# espnative-deadrail-2-b.net
KiCad netlist of a schematic drawn in EAGLE
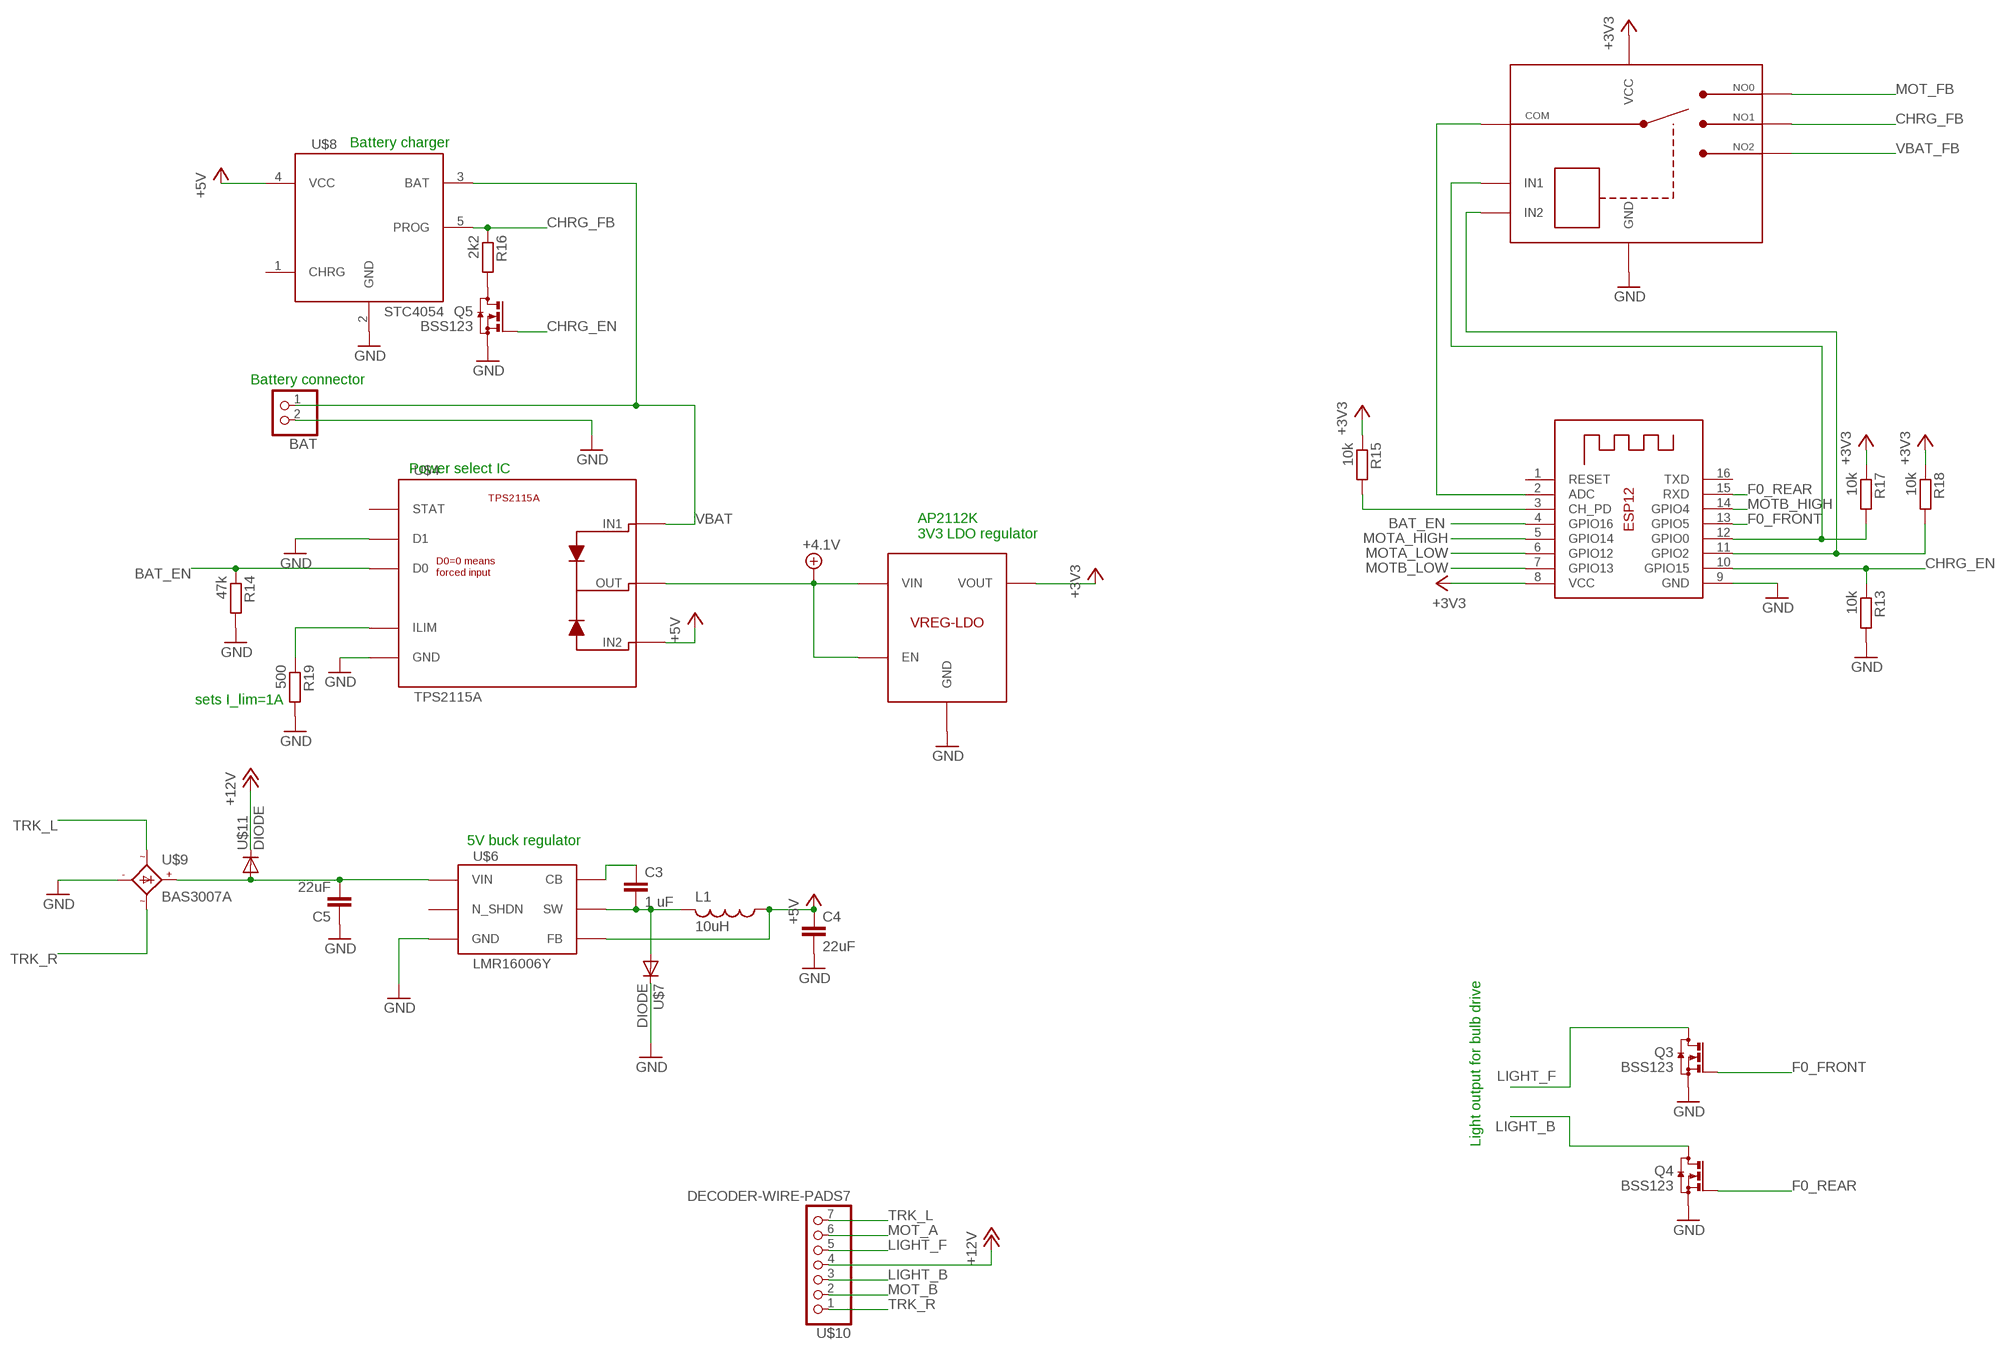
[diagram p0: schematic, sheet 1, part 1 of 2]
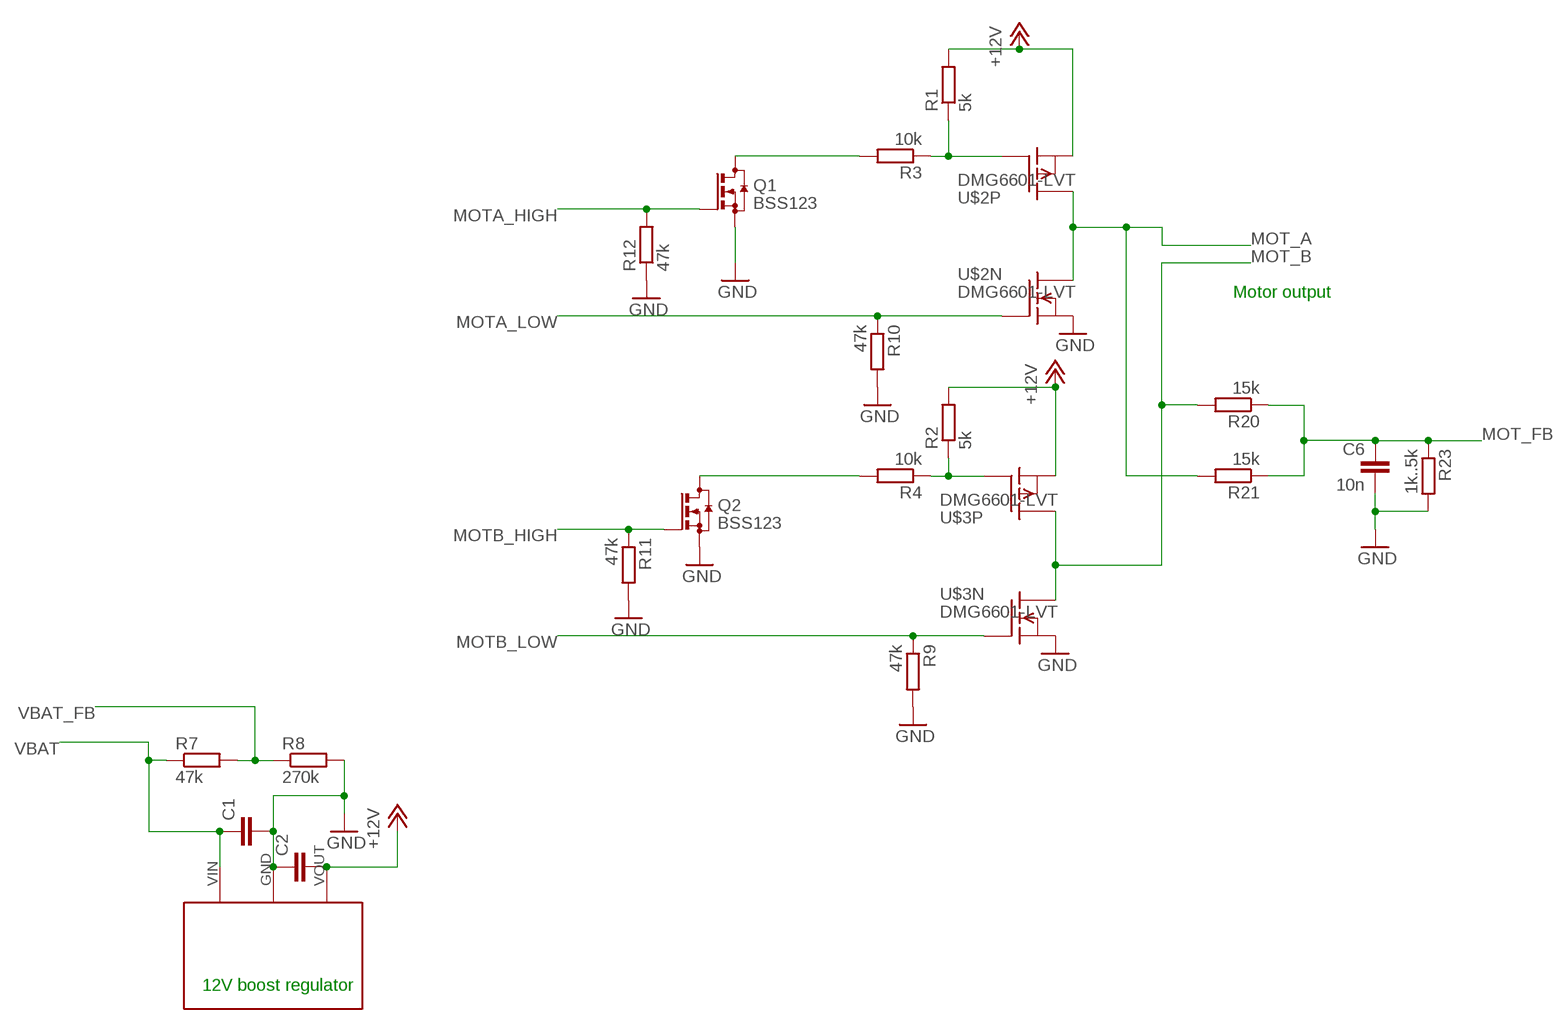
[diagram p1: schematic, sheet 1, part 2 of 2]

(export (version "E")
  (design (tool "Eeschema 10.0.6"))
  (components
    (comp (ref "BAT")
      (value "JST_2PIN-SMT-RA")
      (footprint "eagle-import:JST-PH-2-SMT-RA")
      (libsource (lib "eagle-import") (part "JST_2PIN-SMT-RA"))
    )
    (comp (ref "C1")
      (value "C-EUC1206")
      (footprint "eagle-import:C1206")
      (libsource (lib "eagle-import") (part "C-EUC1206"))
    )
    (comp (ref "C2")
      (value "C-EUC1206")
      (footprint "eagle-import:C1206")
      (libsource (lib "eagle-import") (part "C-EUC1206"))
    )
    (comp (ref "C3")
      (value "1 uF")
      (footprint "eagle-import:C0603")
      (libsource (lib "eagle-import") (part "C-EUC0603"))
    )
    (comp (ref "C4")
      (value "22uF")
      (footprint "eagle-import:C0603")
      (libsource (lib "eagle-import") (part "C-EUC0603"))
    )
    (comp (ref "C5")
      (value "22uF")
      (footprint "eagle-import:C1206")
      (libsource (lib "eagle-import") (part "C-EUC1206"))
    )
    (comp (ref "C6")
      (value "10n")
      (footprint "eagle-import:C0603")
      (libsource (lib "eagle-import") (part "C-EUC0603"))
    )
    (comp (ref "L1")
      (value "10uH")
      (footprint "eagle-import:FDSD0420")
      (libsource (lib "eagle-import") (part "FDSD0420"))
    )
    (comp (ref "Q1")
      (value "BSS123")
      (footprint "eagle-import:SOT23")
      (libsource (lib "eagle-import") (part "BSS123"))
    )
    (comp (ref "Q2")
      (value "BSS123")
      (footprint "eagle-import:SOT23")
      (libsource (lib "eagle-import") (part "BSS123"))
    )
    (comp (ref "Q3")
      (value "BSS123")
      (footprint "eagle-import:SOT23")
      (libsource (lib "eagle-import") (part "BSS123"))
    )
    (comp (ref "Q4")
      (value "BSS123")
      (footprint "eagle-import:SOT23")
      (libsource (lib "eagle-import") (part "BSS123"))
    )
    (comp (ref "Q5")
      (value "BSS123")
      (footprint "eagle-import:SOT23")
      (libsource (lib "eagle-import") (part "BSS123"))
    )
    (comp (ref "R1")
      (value "5k")
      (footprint "eagle-import:R0603")
      (libsource (lib "eagle-import") (part "R-EU_R0603"))
    )
    (comp (ref "R2")
      (value "5k")
      (footprint "eagle-import:R0603")
      (libsource (lib "eagle-import") (part "R-EU_R0603"))
    )
    (comp (ref "R3")
      (value "10k")
      (footprint "eagle-import:R0603")
      (libsource (lib "eagle-import") (part "R-EU_R0603"))
    )
    (comp (ref "R4")
      (value "10k")
      (footprint "eagle-import:R0603")
      (libsource (lib "eagle-import") (part "R-EU_R0603"))
    )
    (comp (ref "R7")
      (value "47k")
      (footprint "eagle-import:R0603")
      (libsource (lib "eagle-import") (part "R-EU_R0603"))
    )
    (comp (ref "R8")
      (value "270k")
      (footprint "eagle-import:R0603")
      (libsource (lib "eagle-import") (part "R-EU_R0603"))
    )
    (comp (ref "R9")
      (value "47k")
      (footprint "eagle-import:R0603")
      (libsource (lib "eagle-import") (part "R-EU_R0603"))
    )
    (comp (ref "R10")
      (value "47k")
      (footprint "eagle-import:R0603")
      (libsource (lib "eagle-import") (part "R-EU_R0603"))
    )
    (comp (ref "R11")
      (value "47k")
      (footprint "eagle-import:R0603")
      (libsource (lib "eagle-import") (part "R-EU_R0603"))
    )
    (comp (ref "R12")
      (value "47k")
      (footprint "eagle-import:R0603")
      (libsource (lib "eagle-import") (part "R-EU_R0603"))
    )
    (comp (ref "R13")
      (value "10k")
      (footprint "eagle-import:R0603")
      (libsource (lib "eagle-import") (part "R-EU_R0603"))
    )
    (comp (ref "R14")
      (value "47k")
      (footprint "eagle-import:R0603")
      (libsource (lib "eagle-import") (part "R-EU_R0603"))
    )
    (comp (ref "R15")
      (value "10k")
      (footprint "eagle-import:R0603")
      (libsource (lib "eagle-import") (part "R-EU_R0603"))
    )
    (comp (ref "R16")
      (value "2k2")
      (footprint "eagle-import:R0603")
      (libsource (lib "eagle-import") (part "R-EU_R0603"))
    )
    (comp (ref "R17")
      (value "10k")
      (footprint "eagle-import:R0603")
      (libsource (lib "eagle-import") (part "R-EU_R0603"))
    )
    (comp (ref "R18")
      (value "10k")
      (footprint "eagle-import:R0603")
      (libsource (lib "eagle-import") (part "R-EU_R0603"))
    )
    (comp (ref "R19")
      (value "500")
      (footprint "eagle-import:R0603")
      (libsource (lib "eagle-import") (part "R-EU_R0603"))
    )
    (comp (ref "R20")
      (value "15k")
      (footprint "eagle-import:R0603")
      (libsource (lib "eagle-import") (part "R-EU_R0603"))
    )
    (comp (ref "R21")
      (value "15k")
      (footprint "eagle-import:R0603")
      (libsource (lib "eagle-import") (part "R-EU_R0603"))
    )
    (comp (ref "R23")
      (value "1k..5k")
      (footprint "eagle-import:R0603")
      (libsource (lib "eagle-import") (part "R-EU_R0603"))
    )
    (comp (ref "U$1")
      (value "AP2112K-3V3")
      (footprint "eagle-import:SOT23-5L")
      (libsource (lib "eagle-import") (part "AP2112K"))
    )
    (comp (ref "U$2")
      (value "DMG6601-LVT")
      (footprint "eagle-import:TSOT-26")
      (libsource (lib "eagle-import") (part "DMG6601-LVT"))
    )
    (comp (ref "U$3")
      (value "DMG6601-LVT")
      (footprint "eagle-import:TSOT-26")
      (libsource (lib "eagle-import") (part "DMG6601-LVT"))
    )
    (comp (ref "U$4")
      (value "TPS2115A")
      (footprint "eagle-import:TSSOP-8")
      (libsource (lib "eagle-import") (part "TPS2115A"))
    )
    (comp (ref "U$5")
      (value "POLOLU-VREG12")
      (footprint "eagle-import:POLOLU-REGULATOR")
      (libsource (lib "eagle-import") (part "POLOLU-VREG12"))
    )
    (comp (ref "U$6")
      (value "LMR16006Y")
      (footprint "eagle-import:SOT23-6")
      (libsource (lib "eagle-import") (part "LMR16006Y"))
    )
    (comp (ref "U$7")
      (value "DIODE")
      (footprint "eagle-import:DIODE-1206")
      (libsource (lib "eagle-import") (part "DIODE"))
    )
    (comp (ref "U$8")
      (value "STC4054")
      (footprint "eagle-import:SOT23-5L")
      (libsource (lib "eagle-import") (part "STC4054"))
    )
    (comp (ref "U$9")
      (value "BAS3007A")
      (footprint "eagle-import:SOT143B")
      (libsource (lib "eagle-import") (part "BAS3007A"))
    )
    (comp (ref "U$10")
      (value "DECODER-WIRE-PADS7")
      (footprint "eagle-import:DECODER-WIRE-PADS")
      (libsource (lib "eagle-import") (part "DECODER-WIRE-PADS7"))
    )
    (comp (ref "U$11")
      (value "DIODE")
      (footprint "eagle-import:DIODE-1206")
      (libsource (lib "eagle-import") (part "DIODE"))
    )
    (comp (ref "U$12")
      (value "TS5A3359")
      (footprint "eagle-import:US8")
      (libsource (lib "eagle-import") (part "TS5A3359"))
    )
    (comp (ref "X1")
      (value "ESP-12")
      (footprint "eagle-import:ESP-12")
      (libsource (lib "eagle-import") (part "ESP-12"))
    )
  )
  (nets
    (net (code "1") (name "+3V3") (class "Default")
      (node (ref "R15") (pin "1") (pinfunction "1_1") (pintype "passive"))
      (node (ref "R17") (pin "1") (pinfunction "1_1") (pintype "passive"))
      (node (ref "R18") (pin "1") (pinfunction "1_1") (pintype "passive"))
      (node (ref "U$1") (pin "5") (pinfunction "VOUT_5") (pintype "bidirectional"))
      (node (ref "U$12") (pin "8") (pinfunction "VCC_8") (pintype "bidirectional"))
      (node (ref "X1") (pin "8") (pinfunction "VCC_8") (pintype "power_in"))
    )
    (net (code "2") (name "+4.1V") (class "Default")
      (node (ref "U$1") (pin "1") (pinfunction "VIN_1") (pintype "bidirectional"))
      (node (ref "U$1") (pin "3") (pinfunction "EN_3") (pintype "bidirectional"))
      (node (ref "U$4") (pin "7") (pinfunction "OUT_7") (pintype "bidirectional"))
    )
    (net (code "3") (name "+5V") (class "Default")
      (node (ref "C4") (pin "1") (pinfunction "1_1") (pintype "passive"))
      (node (ref "L1") (pin "P$1") (pinfunction "1_P$1") (pintype "passive"))
      (node (ref "U$4") (pin "6") (pinfunction "IN2_6") (pintype "bidirectional"))
      (node (ref "U$6") (pin "3") (pinfunction "FB_3") (pintype "bidirectional"))
      (node (ref "U$8") (pin "4") (pinfunction "VCC_4") (pintype "bidirectional"))
    )
    (net (code "4") (name "+12V") (class "Default")
      (node (ref "C2") (pin "2") (pinfunction "2_2") (pintype "passive"))
      (node (ref "R1") (pin "2") (pinfunction "2_2") (pintype "passive"))
      (node (ref "R2") (pin "2") (pinfunction "2_2") (pintype "passive"))
      (node (ref "U$10") (pin "4") (pinfunction "4_4") (pintype "passive"))
      (node (ref "U$11") (pin "C") (pinfunction "C_C") (pintype "passive"))
      (node (ref "U$2") (pin "2") (pinfunction "S_2") (pintype "passive"))
      (node (ref "U$3") (pin "2") (pinfunction "S_2") (pintype "passive"))
      (node (ref "U$5") (pin "VOUT") (pinfunction "VOUT_VOUT") (pintype "bidirectional"))
    )
    (net (code "5") (name "/BAT_EN") (class "Default")
      (node (ref "R14") (pin "1") (pinfunction "1_1") (pintype "passive"))
      (node (ref "U$4") (pin "2") (pinfunction "D0_2") (pintype "bidirectional"))
      (node (ref "X1") (pin "4") (pinfunction "GPIO16_4") (pintype "bidirectional"))
    )
    (net (code "6") (name "/CHRG_EN") (class "Default")
      (node (ref "Q5") (pin "1") (pinfunction "G_1") (pintype "passive"))
      (node (ref "R13") (pin "1") (pinfunction "1_1") (pintype "passive"))
      (node (ref "X1") (pin "10") (pinfunction "GPIO15_10") (pintype "bidirectional"))
    )
    (net (code "7") (name "/CHRG_FB") (class "Default")
      (node (ref "R16") (pin "1") (pinfunction "1_1") (pintype "passive"))
      (node (ref "U$12") (pin "2") (pinfunction "NO1_2") (pintype "bidirectional"))
      (node (ref "U$8") (pin "5") (pinfunction "PROG_5") (pintype "bidirectional"))
    )
    (net (code "8") (name "/F0_FRONT") (class "Default")
      (node (ref "Q3") (pin "1") (pinfunction "G_1") (pintype "passive"))
      (node (ref "X1") (pin "13") (pinfunction "GPIO5_13") (pintype "bidirectional"))
    )
    (net (code "9") (name "/F0_REAR") (class "Default")
      (node (ref "Q4") (pin "1") (pinfunction "G_1") (pintype "passive"))
      (node (ref "X1") (pin "15") (pinfunction "RXD_15") (pintype "input"))
    )
    (net (code "10") (name "/LIGHT_B") (class "Default")
      (node (ref "Q4") (pin "3") (pinfunction "D_3") (pintype "passive"))
      (node (ref "U$10") (pin "3") (pinfunction "3_3") (pintype "passive"))
    )
    (net (code "11") (name "/LIGHT_F") (class "Default")
      (node (ref "Q3") (pin "3") (pinfunction "D_3") (pintype "passive"))
      (node (ref "U$10") (pin "5") (pinfunction "5_5") (pintype "passive"))
    )
    (net (code "12") (name "/MOTA_HIGH") (class "Default")
      (node (ref "Q1") (pin "1") (pinfunction "G_1") (pintype "passive"))
      (node (ref "R12") (pin "2") (pinfunction "2_2") (pintype "passive"))
      (node (ref "X1") (pin "5") (pinfunction "GPIO14_5") (pintype "bidirectional"))
    )
    (net (code "13") (name "/MOTA_LOW") (class "Default")
      (node (ref "R10") (pin "1") (pinfunction "1_1") (pintype "passive"))
      (node (ref "U$2") (pin "1") (pinfunction "G_1") (pintype "passive"))
      (node (ref "X1") (pin "6") (pinfunction "GPIO12_6") (pintype "bidirectional"))
    )
    (net (code "14") (name "/MOTB_HIGH") (class "Default")
      (node (ref "Q2") (pin "1") (pinfunction "G_1") (pintype "passive"))
      (node (ref "R11") (pin "1") (pinfunction "1_1") (pintype "passive"))
      (node (ref "X1") (pin "14") (pinfunction "GPIO4_14") (pintype "bidirectional"))
    )
    (net (code "15") (name "/MOTB_LOW") (class "Default")
      (node (ref "R9") (pin "1") (pinfunction "1_1") (pintype "passive"))
      (node (ref "U$3") (pin "1") (pinfunction "G_1") (pintype "passive"))
      (node (ref "X1") (pin "7") (pinfunction "GPIO13_7") (pintype "bidirectional"))
    )
    (net (code "16") (name "/MOT_A") (class "Default")
      (node (ref "R21") (pin "2") (pinfunction "2_2") (pintype "passive"))
      (node (ref "U$10") (pin "6") (pinfunction "6_6") (pintype "passive"))
      (node (ref "U$2") (pin "4") (pinfunction "D_4") (pintype "passive"))
      (node (ref "U$2") (pin "6") (pinfunction "D_6") (pintype "passive"))
    )
    (net (code "17") (name "/MOT_B") (class "Default")
      (node (ref "R20") (pin "2") (pinfunction "2_2") (pintype "passive"))
      (node (ref "U$10") (pin "2") (pinfunction "2_2") (pintype "passive"))
      (node (ref "U$3") (pin "4") (pinfunction "D_4") (pintype "passive"))
      (node (ref "U$3") (pin "6") (pinfunction "D_6") (pintype "passive"))
    )
    (net (code "18") (name "/MOT_FB") (class "Default")
      (node (ref "C6") (pin "1") (pinfunction "1_1") (pintype "passive"))
      (node (ref "R20") (pin "1") (pinfunction "1_1") (pintype "passive"))
      (node (ref "R21") (pin "1") (pinfunction "1_1") (pintype "passive"))
      (node (ref "R23") (pin "1") (pinfunction "1_1") (pintype "passive"))
      (node (ref "U$12") (pin "1") (pinfunction "NO0_1") (pintype "bidirectional"))
    )
    (net (code "19") (name "/TRK_L") (class "Default")
      (node (ref "U$10") (pin "7") (pinfunction "7_7") (pintype "passive"))
      (node (ref "U$9") (pin "2") (pinfunction "AC1_2") (pintype "passive"))
    )
    (net (code "20") (name "/TRK_R") (class "Default")
      (node (ref "U$10") (pin "1") (pinfunction "1_1") (pintype "passive"))
      (node (ref "U$9") (pin "3") (pinfunction "AC2_3") (pintype "passive"))
    )
    (net (code "21") (name "/VBAT") (class "Default")
      (node (ref "BAT") (pin "1") (pinfunction "2_1") (pintype "passive"))
      (node (ref "C1") (pin "1") (pinfunction "1_1") (pintype "passive"))
      (node (ref "R7") (pin "1") (pinfunction "1_1") (pintype "passive"))
      (node (ref "U$4") (pin "8") (pinfunction "IN1_8") (pintype "bidirectional"))
      (node (ref "U$5") (pin "VIN") (pinfunction "VIN_VIN") (pintype "bidirectional"))
      (node (ref "U$8") (pin "3") (pinfunction "BAT_3") (pintype "bidirectional"))
    )
    (net (code "22") (name "/VBAT_FB") (class "Default")
      (node (ref "R7") (pin "2") (pinfunction "2_2") (pintype "passive"))
      (node (ref "R8") (pin "1") (pinfunction "1_1") (pintype "passive"))
      (node (ref "U$12") (pin "3") (pinfunction "NO2_3") (pintype "bidirectional"))
    )
    (net (code "23") (name "GND") (class "Default")
      (node (ref "BAT") (pin "2") (pinfunction "1_2") (pintype "passive"))
      (node (ref "C1") (pin "2") (pinfunction "2_2") (pintype "passive"))
      (node (ref "C2") (pin "1") (pinfunction "1_1") (pintype "passive"))
      (node (ref "C4") (pin "2") (pinfunction "2_2") (pintype "passive"))
      (node (ref "C5") (pin "1") (pinfunction "1_1") (pintype "passive"))
      (node (ref "C6") (pin "2") (pinfunction "2_2") (pintype "passive"))
      (node (ref "Q1") (pin "2") (pinfunction "S_2") (pintype "passive"))
      (node (ref "Q2") (pin "2") (pinfunction "S_2") (pintype "passive"))
      (node (ref "Q3") (pin "2") (pinfunction "S_2") (pintype "passive"))
      (node (ref "Q4") (pin "2") (pinfunction "S_2") (pintype "passive"))
      (node (ref "Q5") (pin "2") (pinfunction "S_2") (pintype "passive"))
      (node (ref "R10") (pin "2") (pinfunction "2_2") (pintype "passive"))
      (node (ref "R11") (pin "2") (pinfunction "2_2") (pintype "passive"))
      (node (ref "R12") (pin "1") (pinfunction "1_1") (pintype "passive"))
      (node (ref "R13") (pin "2") (pinfunction "2_2") (pintype "passive"))
      (node (ref "R14") (pin "2") (pinfunction "2_2") (pintype "passive"))
      (node (ref "R19") (pin "2") (pinfunction "2_2") (pintype "passive"))
      (node (ref "R23") (pin "2") (pinfunction "2_2") (pintype "passive"))
      (node (ref "R8") (pin "2") (pinfunction "2_2") (pintype "passive"))
      (node (ref "R9") (pin "2") (pinfunction "2_2") (pintype "passive"))
      (node (ref "U$1") (pin "2") (pinfunction "GND_2") (pintype "bidirectional"))
      (node (ref "U$12") (pin "4") (pinfunction "GND_4") (pintype "bidirectional"))
      (node (ref "U$2") (pin "5") (pinfunction "S_5") (pintype "passive"))
      (node (ref "U$3") (pin "5") (pinfunction "S_5") (pintype "passive"))
      (node (ref "U$4") (pin "3") (pinfunction "D1_3") (pintype "bidirectional"))
      (node (ref "U$4") (pin "5") (pinfunction "GND_5") (pintype "bidirectional"))
      (node (ref "U$5") (pin "GND") (pinfunction "GND_GND") (pintype "bidirectional"))
      (node (ref "U$6") (pin "2") (pinfunction "GND_2") (pintype "bidirectional"))
      (node (ref "U$7") (pin "C") (pinfunction "C_C") (pintype "passive"))
      (node (ref "U$8") (pin "2") (pinfunction "GND_2") (pintype "bidirectional"))
      (node (ref "U$9") (pin "1") (pinfunction "-_1") (pintype "passive"))
      (node (ref "X1") (pin "9") (pinfunction "GND_9") (pintype "power_in"))
    )
    (net (code "24") (name "Net-(L1-2)") (class "Default")
      (node (ref "C3") (pin "2") (pinfunction "2_2") (pintype "passive"))
      (node (ref "L1") (pin "P$2") (pinfunction "2_P$2") (pintype "passive"))
      (node (ref "U$6") (pin "6") (pinfunction "SW_6") (pintype "bidirectional"))
      (node (ref "U$7") (pin "A") (pinfunction "A_A") (pintype "passive"))
    )
    (net (code "25") (name "Net-(Q1-D)") (class "Default")
      (node (ref "Q1") (pin "3") (pinfunction "D_3") (pintype "passive"))
      (node (ref "R3") (pin "2") (pinfunction "2_2") (pintype "passive"))
    )
    (net (code "26") (name "Net-(Q2-D)") (class "Default")
      (node (ref "Q2") (pin "3") (pinfunction "D_3") (pintype "passive"))
      (node (ref "R4") (pin "2") (pinfunction "2_2") (pintype "passive"))
    )
    (net (code "27") (name "Net-(Q5-D)") (class "Default")
      (node (ref "Q5") (pin "3") (pinfunction "D_3") (pintype "passive"))
      (node (ref "R16") (pin "2") (pinfunction "2_2") (pintype "passive"))
    )
    (net (code "28") (name "Net-(U$2B-G)") (class "Default")
      (node (ref "R1") (pin "1") (pinfunction "1_1") (pintype "passive"))
      (node (ref "R3") (pin "1") (pinfunction "1_1") (pintype "passive"))
      (node (ref "U$2") (pin "3") (pinfunction "G_3") (pintype "passive"))
    )
    (net (code "29") (name "Net-(U$3B-G)") (class "Default")
      (node (ref "R2") (pin "1") (pinfunction "1_1") (pintype "passive"))
      (node (ref "R4") (pin "1") (pinfunction "1_1") (pintype "passive"))
      (node (ref "U$3") (pin "3") (pinfunction "G_3") (pintype "passive"))
    )
    (net (code "30") (name "Net-(U$4-ILIM)") (class "Default")
      (node (ref "R19") (pin "1") (pinfunction "1_1") (pintype "passive"))
      (node (ref "U$4") (pin "4") (pinfunction "ILIM_4") (pintype "bidirectional"))
    )
    (net (code "31") (name "Net-(U$6-CB)") (class "Default")
      (node (ref "C3") (pin "1") (pinfunction "1_1") (pintype "passive"))
      (node (ref "U$6") (pin "1") (pinfunction "CB_1") (pintype "bidirectional"))
    )
    (net (code "32") (name "Net-(U$6-VIN)") (class "Default")
      (node (ref "C5") (pin "2") (pinfunction "2_2") (pintype "passive"))
      (node (ref "U$11") (pin "A") (pinfunction "A_A") (pintype "passive"))
      (node (ref "U$6") (pin "5") (pinfunction "VIN_5") (pintype "bidirectional"))
      (node (ref "U$9") (pin "4") (pinfunction "+_4") (pintype "passive"))
    )
    (net (code "33") (name "Net-(U$12-COM)") (class "Default")
      (node (ref "U$12") (pin "7") (pinfunction "COM_7") (pintype "bidirectional"))
      (node (ref "X1") (pin "2") (pinfunction "ADC_2") (pintype "passive"))
    )
    (net (code "34") (name "Net-(U$12-IN1)") (class "Default")
      (node (ref "R17") (pin "2") (pinfunction "2_2") (pintype "passive"))
      (node (ref "U$12") (pin "6") (pinfunction "IN1_6") (pintype "bidirectional"))
      (node (ref "X1") (pin "12") (pinfunction "GPIO0_12") (pintype "bidirectional"))
    )
    (net (code "35") (name "Net-(U$12-IN2)") (class "Default")
      (node (ref "R18") (pin "2") (pinfunction "2_2") (pintype "passive"))
      (node (ref "U$12") (pin "5") (pinfunction "IN2_5") (pintype "bidirectional"))
      (node (ref "X1") (pin "11") (pinfunction "GPIO2_11") (pintype "bidirectional"))
    )
    (net (code "36") (name "Net-(X1-CH_PD)") (class "Default")
      (node (ref "R15") (pin "2") (pinfunction "2_2") (pintype "passive"))
      (node (ref "X1") (pin "3") (pinfunction "CH_PD_3") (pintype "input"))
    )
    (net (code "37") (name "unconnected-(U$4-STAT-Pad1)") (class "Default")
      (node (ref "U$4") (pin "1") (pinfunction "STAT_1") (pintype "bidirectional"))
    )
    (net (code "38") (name "unconnected-(U$6-N_SHDN-Pad4)") (class "Default")
      (node (ref "U$6") (pin "4") (pinfunction "N_SHDN_4") (pintype "bidirectional"))
    )
    (net (code "39") (name "unconnected-(U$8-CHRG-Pad1)") (class "Default")
      (node (ref "U$8") (pin "1") (pinfunction "CHRG_1") (pintype "bidirectional"))
    )
    (net (code "40") (name "unconnected-(X1-RESET-Pad1)") (class "Default")
      (node (ref "X1") (pin "1") (pinfunction "RESET_1") (pintype "input"))
    )
    (net (code "41") (name "unconnected-(X1-TXD-Pad16)") (class "Default")
      (node (ref "X1") (pin "16") (pinfunction "TXD_16") (pintype "output"))
    )
  )
)
